# v3a.net
KiCad netlist of a schematic drawn in EAGLE
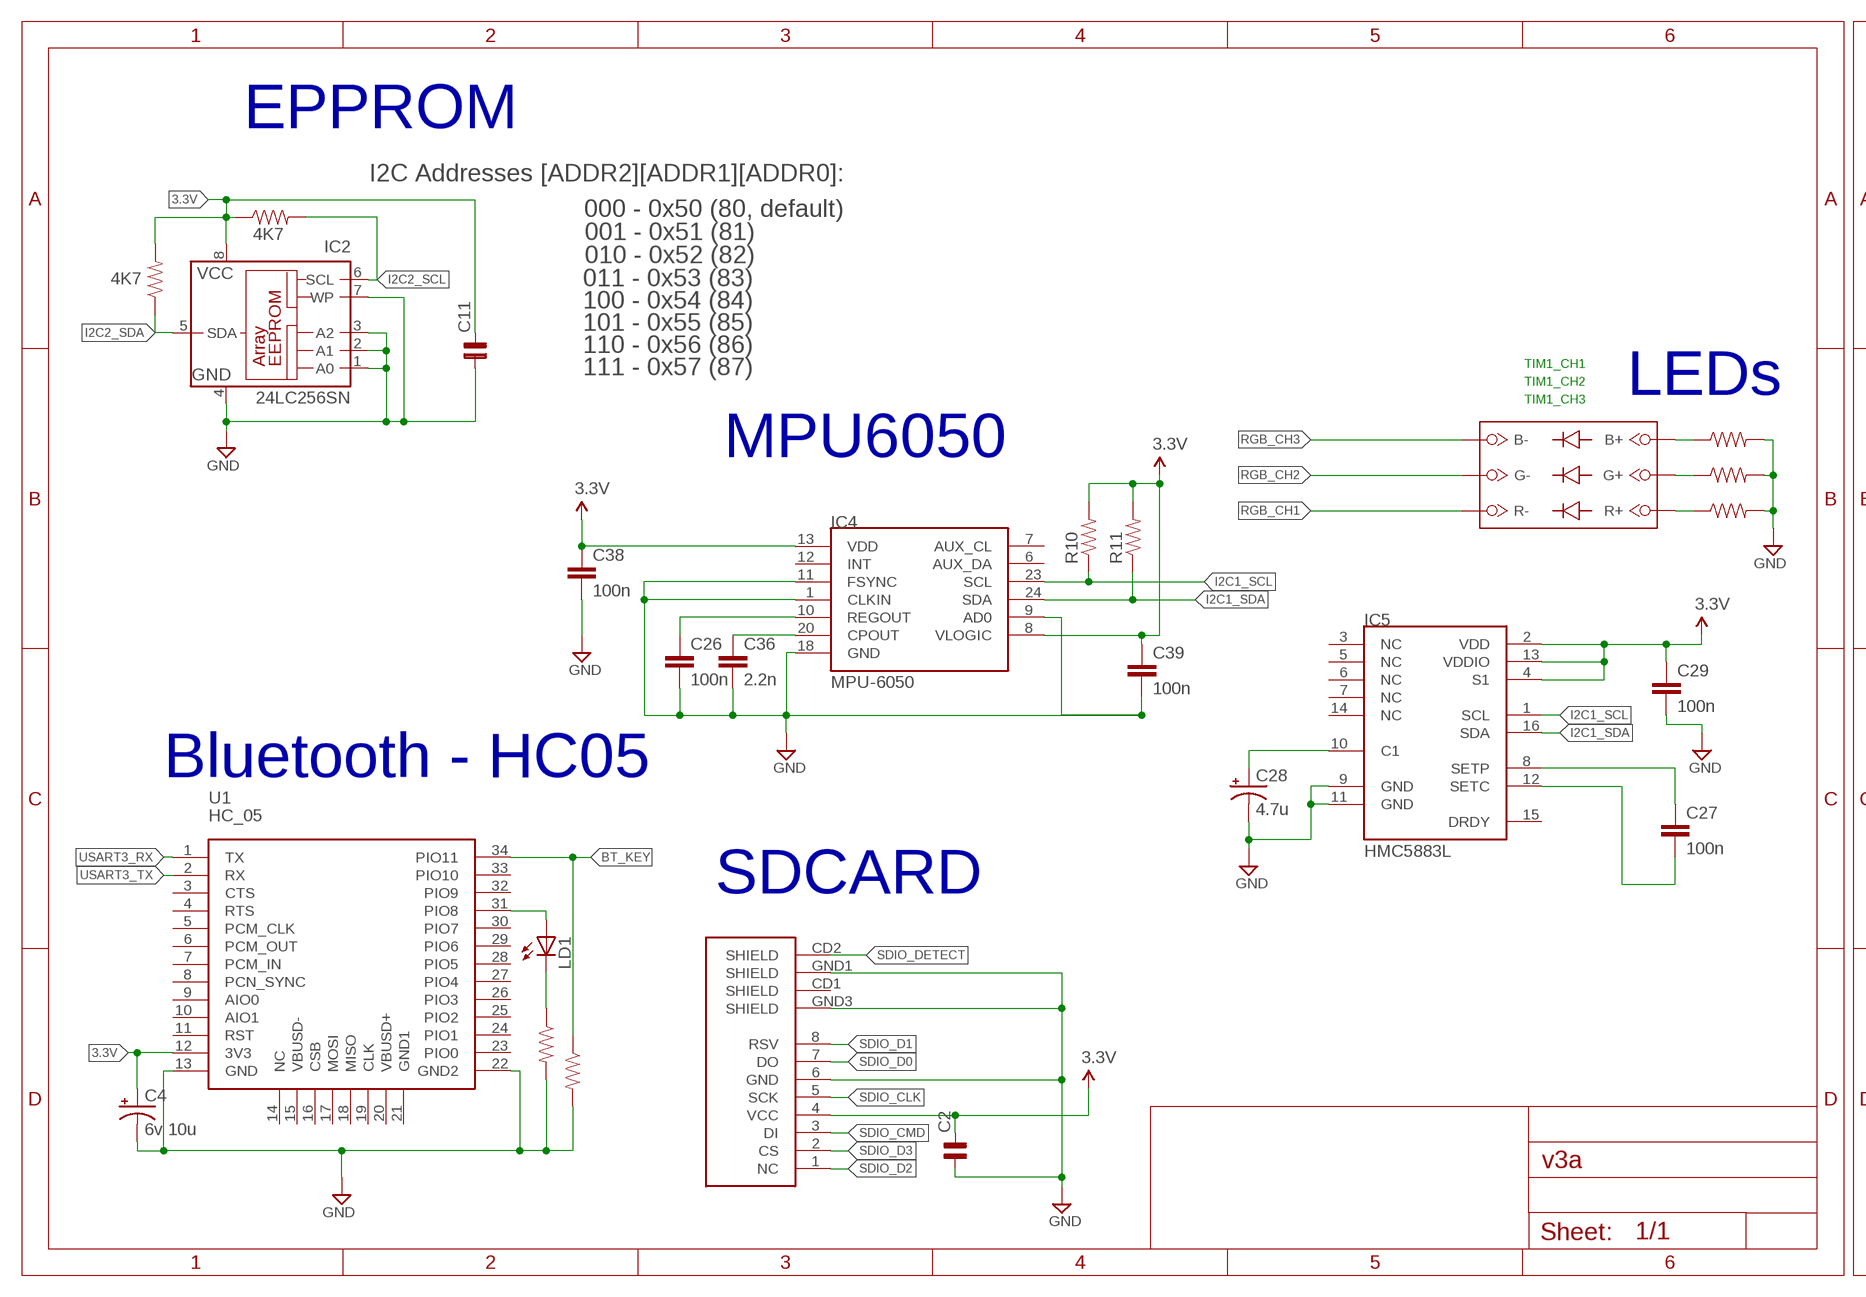
[diagram p0: schematic, sheet 1, part 1 of 2]
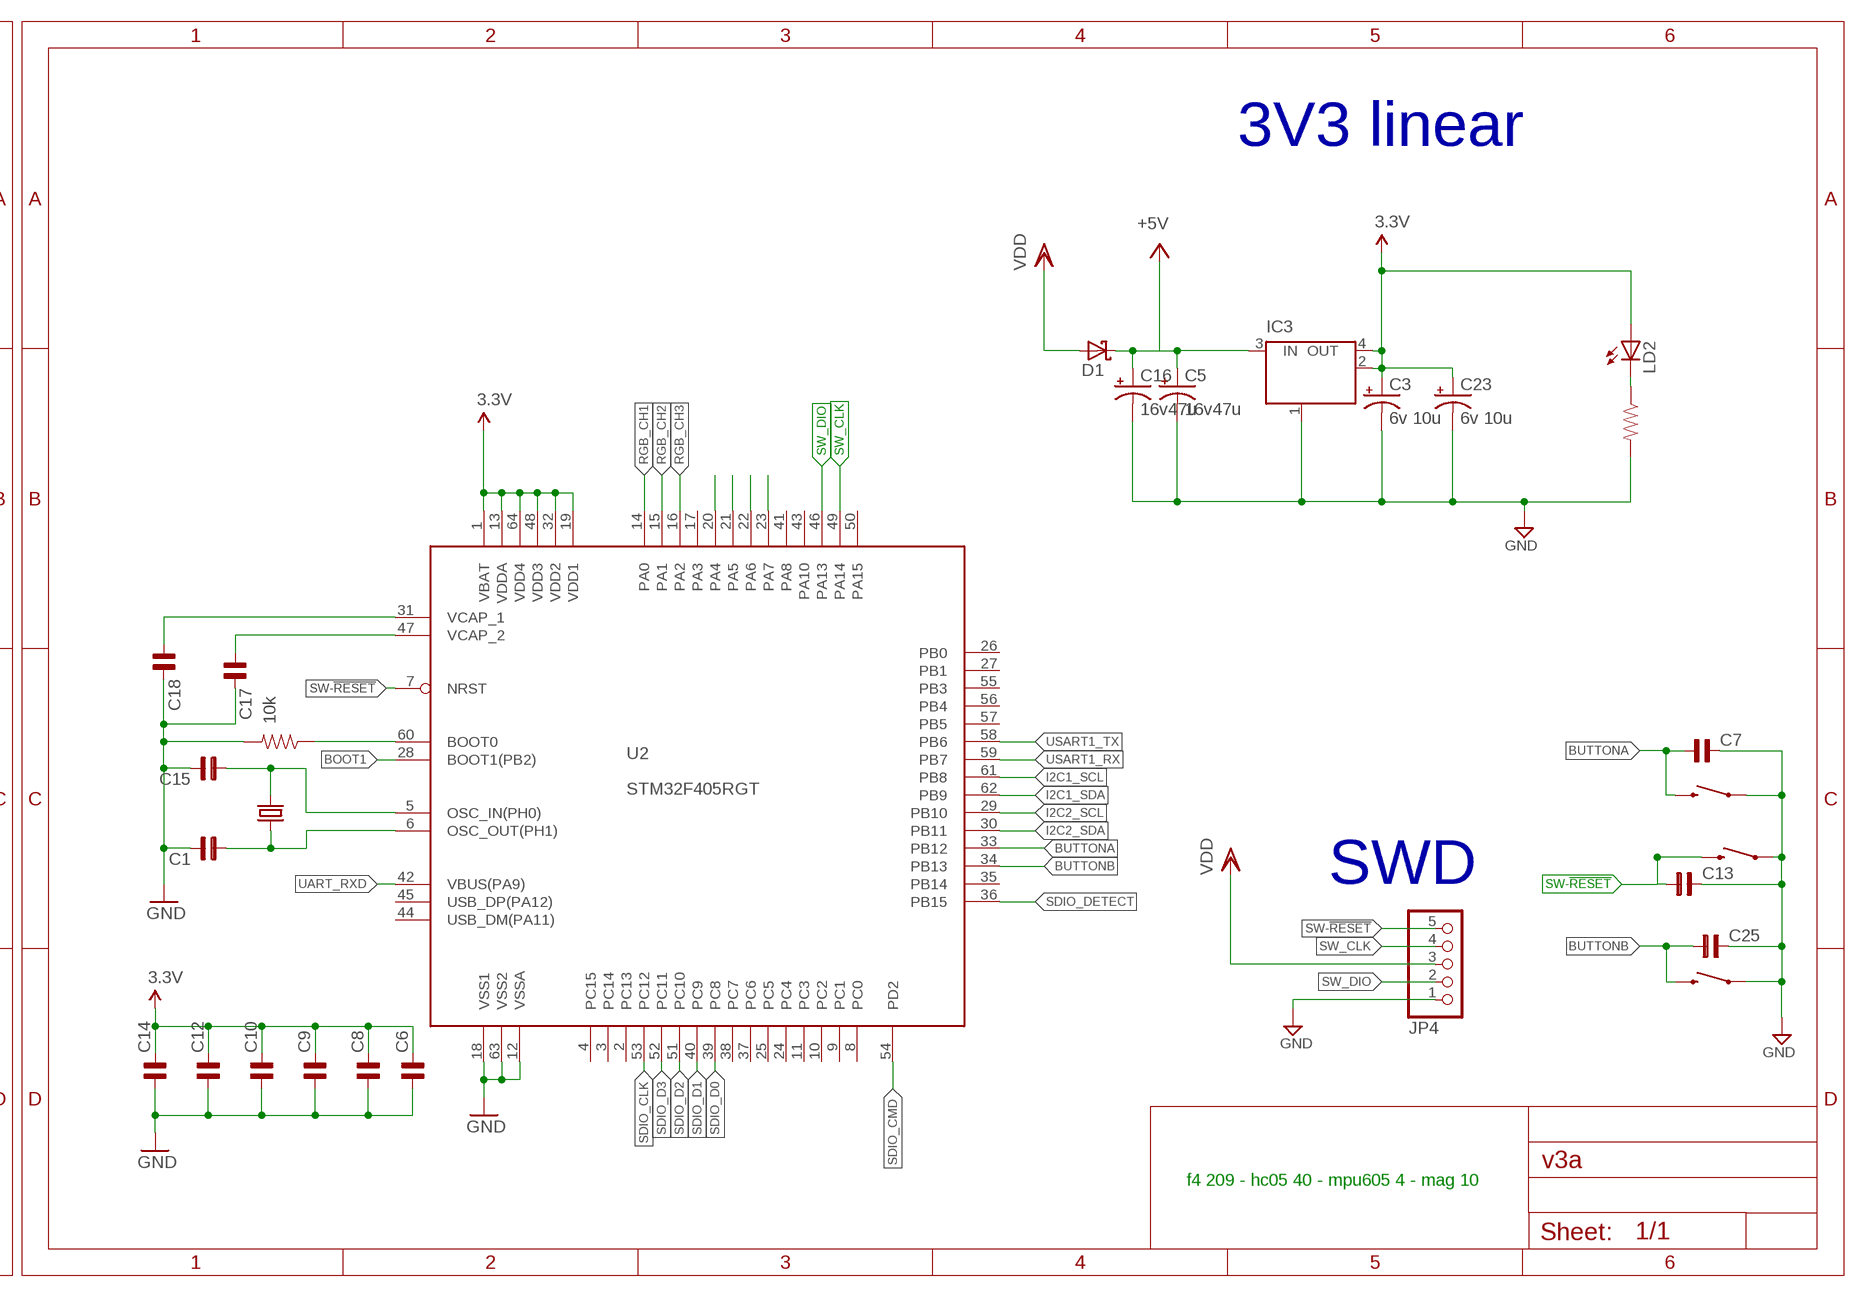
[diagram p1: schematic, sheet 1, part 2 of 2]

(export (version "E")
  (design (tool "Eeschema 10.0.6"))
  (components
    (comp (ref "C1")
      (value "C-NP-SMD-0603")
      (footprint "eagle-import:C-0603")
      (libsource (lib "eagle-import") (part "C-NP-SMD-0603"))
    )
    (comp (ref "C2")
      (value "C-NP-SMD-0603")
      (footprint "eagle-import:C-0603")
      (libsource (lib "eagle-import") (part "C-NP-SMD-0603"))
    )
    (comp (ref "C3")
      (value "6v 10u")
      (footprint "eagle-import:SMC_C")
      (libsource (lib "eagle-import") (part "CPOL-USSMCC"))
    )
    (comp (ref "C4")
      (value "6v 10u")
      (footprint "eagle-import:SMC_A")
      (libsource (lib "eagle-import") (part "CPOL-USSMCA"))
    )
    (comp (ref "C5")
      (value "16v47u")
      (footprint "eagle-import:SMC_C")
      (libsource (lib "eagle-import") (part "CPOL-USSMCC"))
    )
    (comp (ref "C6")
      (value "C-NP-SMD-0603")
      (footprint "eagle-import:C-0603")
      (libsource (lib "eagle-import") (part "C-NP-SMD-0603"))
    )
    (comp (ref "C7")
      (value "C-NP-SMD-0603")
      (footprint "eagle-import:C-0603")
      (libsource (lib "eagle-import") (part "C-NP-SMD-0603"))
    )
    (comp (ref "C8")
      (value "C-NP-SMD-0603")
      (footprint "eagle-import:C-0603")
      (libsource (lib "eagle-import") (part "C-NP-SMD-0603"))
    )
    (comp (ref "C9")
      (value "C-NP-SMD-0603")
      (footprint "eagle-import:C-0603")
      (libsource (lib "eagle-import") (part "C-NP-SMD-0603"))
    )
    (comp (ref "C10")
      (value "C-NP-SMD-0603")
      (footprint "eagle-import:C-0603")
      (libsource (lib "eagle-import") (part "C-NP-SMD-0603"))
    )
    (comp (ref "C11")
      (value "C-NP-SMD-0603")
      (footprint "eagle-import:C-0603")
      (libsource (lib "eagle-import") (part "C-NP-SMD-0603"))
    )
    (comp (ref "C12")
      (value "C-NP-SMD-0603")
      (footprint "eagle-import:C-0603")
      (libsource (lib "eagle-import") (part "C-NP-SMD-0603"))
    )
    (comp (ref "C13")
      (value "C-NP-SMD-0603")
      (footprint "eagle-import:C-0603")
      (libsource (lib "eagle-import") (part "C-NP-SMD-0603"))
    )
    (comp (ref "C14")
      (value "C-NP-SMD-0603")
      (footprint "eagle-import:C-0603")
      (libsource (lib "eagle-import") (part "C-NP-SMD-0603"))
    )
    (comp (ref "C15")
      (value "C-NP-SMD-0603")
      (footprint "eagle-import:C-0603")
      (libsource (lib "eagle-import") (part "C-NP-SMD-0603"))
    )
    (comp (ref "C16")
      (value "16v47u")
      (footprint "eagle-import:SMC_C")
      (libsource (lib "eagle-import") (part "CPOL-USSMCC"))
    )
    (comp (ref "C17")
      (value "C-NP-SMD-0603")
      (footprint "eagle-import:C-0603")
      (libsource (lib "eagle-import") (part "C-NP-SMD-0603"))
    )
    (comp (ref "C18")
      (value "C-NP-SMD-0603")
      (footprint "eagle-import:C-0603")
      (libsource (lib "eagle-import") (part "C-NP-SMD-0603"))
    )
    (comp (ref "C23")
      (value "6v 10u")
      (footprint "eagle-import:SMC_C")
      (libsource (lib "eagle-import") (part "CPOL-USSMCC"))
    )
    (comp (ref "C25")
      (value "C-NP-SMD-0603")
      (footprint "eagle-import:C-0603")
      (libsource (lib "eagle-import") (part "C-NP-SMD-0603"))
    )
    (comp (ref "C26")
      (value "100n")
      (footprint "eagle-import:SPARKFUN_0603-CAP")
      (libsource (lib "eagle-import") (part "SPARKFUN_CAP0603-CAP"))
    )
    (comp (ref "C27")
      (value "100n")
      (footprint "eagle-import:SPARKFUN_0603-CAP")
      (libsource (lib "eagle-import") (part "SPARKFUN_CAP0603-CAP"))
    )
    (comp (ref "C28")
      (value "4.7u")
      (footprint "eagle-import:SMC_A")
      (libsource (lib "eagle-import") (part "CPOL-USSMCA"))
    )
    (comp (ref "C29")
      (value "100n")
      (footprint "eagle-import:SPARKFUN_0603-CAP")
      (libsource (lib "eagle-import") (part "SPARKFUN_CAP0603-CAP"))
    )
    (comp (ref "C36")
      (value "2.2n")
      (footprint "eagle-import:SPARKFUN_0603-CAP")
      (libsource (lib "eagle-import") (part "SPARKFUN_CAP0603-CAP"))
    )
    (comp (ref "C38")
      (value "100n")
      (footprint "eagle-import:SPARKFUN_0603-CAP")
      (libsource (lib "eagle-import") (part "SPARKFUN_CAP0603-CAP"))
    )
    (comp (ref "C39")
      (value "100n")
      (footprint "eagle-import:SPARKFUN_0603-CAP")
      (libsource (lib "eagle-import") (part "SPARKFUN_CAP0603-CAP"))
    )
    (comp (ref "D1")
      (value "MBRS330T3")
      (footprint "eagle-import:SMC")
      (libsource (lib "eagle-import") (part "MBRS30T33"))
    )
    (comp (ref "IC2")
      (value "24LC256SN")
      (footprint "eagle-import:SO-08")
      (fields (field (name "MF") "MICROCHIP") (field (name "MPN") "24LC256-I/SN"))
      (libsource (lib "eagle-import") (part "24SNLC256"))
    )
    (comp (ref "IC3")
      (value "LINEAR_MC33269ST-3.3T3")
      (footprint "eagle-import:LINEAR_SOT223")
      (libsource (lib "eagle-import") (part "LINEAR_MC33269ST-3.3T3"))
    )
    (comp (ref "IC4")
      (value "MPU-6050")
      (footprint "eagle-import:TESTING_QFN-24-4MM2")
      (libsource (lib "eagle-import") (part "TESTING_MPU-6050-1"))
    )
    (comp (ref "IC5")
      (value "HMC5883L")
      (footprint "eagle-import:SPARKFUN_16LPCC")
      (libsource (lib "eagle-import") (part "SPARKFUN_HMC5883LSMD"))
    )
    (comp (ref "JP4")
      (value "PINHD-1X5_2.54-90°")
      (footprint "eagle-import:1X05_90")
      (libsource (lib "eagle-import") (part "PINHD-1X5_2.54-90°"))
    )
    (comp (ref "LD1")
      (value "LEDCHIPLED_0603")
      (footprint "eagle-import:CHIPLED_0603")
      (libsource (lib "eagle-import") (part "LEDCHIPLED_0603"))
    )
    (comp (ref "LD2")
      (value "LEDCHIPLED_0603")
      (footprint "eagle-import:CHIPLED_0603")
      (libsource (lib "eagle-import") (part "LEDCHIPLED_0603"))
    )
    (comp (ref "R1")
      (value "10K")
      (footprint "eagle-import:SPARKFUN_0603-RES")
      (libsource (lib "eagle-import") (part "Robotech_RCL_SPARKFUN_RESISTOR0603-RES"))
    )
    (comp (ref "R2")
      (value "10K")
      (footprint "eagle-import:SPARKFUN_0603-RES")
      (libsource (lib "eagle-import") (part "Robotech_RCL_SPARKFUN_RESISTOR0603-RES"))
    )
    (comp (ref "R3")
      (value "10K")
      (footprint "eagle-import:SPARKFUN_0603-RES")
      (libsource (lib "eagle-import") (part "Robotech_RCL_SPARKFUN_RESISTOR0603-RES"))
    )
    (comp (ref "R5")
      (value "10K")
      (footprint "eagle-import:SPARKFUN_0603-RES")
      (libsource (lib "eagle-import") (part "Robotech_RCL_SPARKFUN_RESISTOR0603-RES"))
    )
    (comp (ref "R6")
      (value "10K")
      (footprint "eagle-import:SPARKFUN_0603-RES")
      (libsource (lib "eagle-import") (part "Robotech_RCL_SPARKFUN_RESISTOR0603-RES"))
    )
    (comp (ref "R7")
      (value "10k")
      (footprint "eagle-import:SPARKFUN_0603-RES")
      (libsource (lib "eagle-import") (part "Robotech_RCL_SPARKFUN_RESISTOR0603-RES"))
    )
    (comp (ref "R9")
      (value "10K")
      (footprint "eagle-import:SPARKFUN_0603-RES")
      (libsource (lib "eagle-import") (part "Robotech_RCL_SPARKFUN_RESISTOR0603-RES"))
    )
    (comp (ref "R10")
      (value "SPARKFUN_RESISTOR0603-RES")
      (footprint "eagle-import:SPARKFUN_0603-RES")
      (libsource (lib "eagle-import") (part "SPARKFUN_RESISTOR0603-RES"))
    )
    (comp (ref "R11")
      (value "SPARKFUN_RESISTOR0603-RES")
      (footprint "eagle-import:SPARKFUN_0603-RES")
      (libsource (lib "eagle-import") (part "SPARKFUN_RESISTOR0603-RES"))
    )
    (comp (ref "R15")
      (value "4K7")
      (footprint "eagle-import:SPARKFUN_0603-RES")
      (libsource (lib "eagle-import") (part "Robotech_RCL_SPARKFUN_RESISTOR0603-RES"))
    )
    (comp (ref "R16")
      (value "4K7")
      (footprint "eagle-import:SPARKFUN_0603-RES")
      (libsource (lib "eagle-import") (part "Robotech_RCL_SPARKFUN_RESISTOR0603-RES"))
    )
    (comp (ref "S1")
      (value "RESET")
      (footprint "eagle-import:TACTILE-SWITCH-1101NE")
      (fields (field (name "PARTNO") "EVQ-P7J01P"))
      (libsource (lib "eagle-import") (part "SWITCH-MOMENTARY-2-SMD-1101NE"))
    )
    (comp (ref "S2")
      (value "RESET")
      (footprint "eagle-import:TACTILE-SWITCH-1101NE")
      (fields (field (name "PARTNO") "EVQ-P7J01P"))
      (libsource (lib "eagle-import") (part "SWITCH-MOMENTARY-2-SMD-1101NE"))
    )
    (comp (ref "S4")
      (value "RESET")
      (footprint "eagle-import:TACTILE-SWITCH-1101NE")
      (fields (field (name "PARTNO") "EVQ-P7J01P"))
      (libsource (lib "eagle-import") (part "SWITCH-MOMENTARY-2-SMD-1101NE"))
    )
    (comp (ref "SDCARD2")
      (value "microSD Socket")
      (footprint "eagle-import:MICRO-SD-SOCKET-PP")
      (libsource (lib "eagle-import") (part "USD-SOCKETNEW"))
    )
    (comp (ref "U$12")
      (value "RGB_LED")
      (footprint "eagle-import:SMD")
      (libsource (lib "eagle-import") (part "RGB_LED"))
    )
    (comp (ref "U1")
      (value "HC_05")
      (footprint "eagle-import:BLUETOOTH_SMD")
      (libsource (lib "eagle-import") (part "HC_05"))
    )
    (comp (ref "U2")
      (value "STM32F405RGT")
      (footprint "eagle-import:LQFP64")
      (libsource (lib "eagle-import") (part "STM32F405RGT"))
    )
    (comp (ref "Y2")
      (value "CRYSTALHC49US")
      (footprint "eagle-import:HC49US")
      (libsource (lib "eagle-import") (part "CRYSTALHC49US"))
    )
  )
  (nets
    (net (code "1") (name "+5V") (class "Default")
      (node (ref "C16") (pin "+") (pinfunction "+_+") (pintype "passive"))
      (node (ref "C5") (pin "+") (pinfunction "+_+") (pintype "passive"))
      (node (ref "D1") (pin "C") (pinfunction "C_C") (pintype "passive"))
      (node (ref "IC3") (pin "3") (pinfunction "IN_3") (pintype "input"))
    )
    (net (code "2") (name "/SW-~{RESET}") (class "Default")
      (node (ref "C13") (pin "1") (pinfunction "1_1") (pintype "passive"))
      (node (ref "JP4") (pin "5") (pinfunction "5_5") (pintype "passive"))
      (node (ref "S1") (pin "P$2") (pinfunction "2_P$2") (pintype "passive"))
      (node (ref "U2") (pin "7") (pinfunction "NRST_7") (pintype "input"))
    )
    (net (code "3") (name "3.3V") (class "Default")
      (node (ref "C10") (pin "2") (pinfunction "2_2") (pintype "passive"))
      (node (ref "C11") (pin "2") (pinfunction "2_2") (pintype "passive"))
      (node (ref "C12") (pin "2") (pinfunction "2_2") (pintype "passive"))
      (node (ref "C14") (pin "2") (pinfunction "2_2") (pintype "passive"))
      (node (ref "C2") (pin "2") (pinfunction "2_2") (pintype "passive"))
      (node (ref "C23") (pin "+") (pinfunction "+_+") (pintype "passive"))
      (node (ref "C29") (pin "1") (pinfunction "1_1") (pintype "passive"))
      (node (ref "C3") (pin "+") (pinfunction "+_+") (pintype "passive"))
      (node (ref "C38") (pin "1") (pinfunction "1_1") (pintype "passive"))
      (node (ref "C39") (pin "1") (pinfunction "1_1") (pintype "passive"))
      (node (ref "C4") (pin "+") (pinfunction "+_+") (pintype "passive"))
      (node (ref "C6") (pin "2") (pinfunction "2_2") (pintype "passive"))
      (node (ref "C8") (pin "2") (pinfunction "2_2") (pintype "passive"))
      (node (ref "C9") (pin "2") (pinfunction "2_2") (pintype "passive"))
      (node (ref "IC2") (pin "8") (pinfunction "VCC_8") (pintype "power_in"))
      (node (ref "IC3") (pin "2") (pinfunction "OUT_2") (pintype "passive"))
      (node (ref "IC3") (pin "4") (pinfunction "OUT_4") (pintype "passive"))
      (node (ref "IC4") (pin "13") (pinfunction "VDD_13") (pintype "bidirectional"))
      (node (ref "IC4") (pin "8") (pinfunction "VLOGIC_8") (pintype "bidirectional"))
      (node (ref "IC5") (pin "13") (pinfunction "VDDIO_13") (pintype "bidirectional"))
      (node (ref "IC5") (pin "2") (pinfunction "VDD_2") (pintype "bidirectional"))
      (node (ref "IC5") (pin "4") (pinfunction "S1_4") (pintype "bidirectional"))
      (node (ref "LD2") (pin "A") (pinfunction "A_A") (pintype "passive"))
      (node (ref "R10") (pin "2") (pinfunction "2_2") (pintype "passive"))
      (node (ref "R11") (pin "2") (pinfunction "2_2") (pintype "passive"))
      (node (ref "R15") (pin "1") (pinfunction "1_1") (pintype "passive"))
      (node (ref "R16") (pin "2") (pinfunction "2_2") (pintype "passive"))
      (node (ref "SDCARD2") (pin "4") (pinfunction "VCC_4") (pintype "bidirectional"))
      (node (ref "U1") (pin "12") (pinfunction "3V3_12") (pintype "bidirectional"))
      (node (ref "U2") (pin "1") (pinfunction "VBAT_1") (pintype "power_in"))
      (node (ref "U2") (pin "13") (pinfunction "VDDA_13") (pintype "power_in"))
      (node (ref "U2") (pin "19") (pinfunction "VDD1_19") (pintype "power_in"))
      (node (ref "U2") (pin "32") (pinfunction "VDD2_32") (pintype "power_in"))
      (node (ref "U2") (pin "48") (pinfunction "VDD3_48") (pintype "power_in"))
      (node (ref "U2") (pin "64") (pinfunction "VDD4_64") (pintype "power_in"))
    )
    (net (code "4") (name "BOOT1") (class "Default")
      (node (ref "U2") (pin "28") (pinfunction "BOOT1(PB2)_28") (pintype "input"))
    )
    (net (code "5") (name "BT_KEY") (class "Default")
      (node (ref "R5") (pin "1") (pinfunction "1_1") (pintype "passive"))
      (node (ref "U1") (pin "34") (pinfunction "PIO11_34") (pintype "bidirectional"))
    )
    (net (code "6") (name "BUTTONA") (class "Default")
      (node (ref "C7") (pin "1") (pinfunction "1_1") (pintype "passive"))
      (node (ref "S4") (pin "P$2") (pinfunction "2_P$2") (pintype "passive"))
      (node (ref "U2") (pin "33") (pinfunction "PB12_33") (pintype "bidirectional"))
    )
    (net (code "7") (name "BUTTONB") (class "Default")
      (node (ref "C25") (pin "1") (pinfunction "1_1") (pintype "passive"))
      (node (ref "S2") (pin "P$2") (pinfunction "2_P$2") (pintype "passive"))
      (node (ref "U2") (pin "34") (pinfunction "PB13_34") (pintype "bidirectional"))
    )
    (net (code "8") (name "GND") (class "Default")
      (node (ref "C1") (pin "2") (pinfunction "2_2") (pintype "passive"))
      (node (ref "C10") (pin "1") (pinfunction "1_1") (pintype "passive"))
      (node (ref "C11") (pin "1") (pinfunction "1_1") (pintype "passive"))
      (node (ref "C12") (pin "1") (pinfunction "1_1") (pintype "passive"))
      (node (ref "C13") (pin "2") (pinfunction "2_2") (pintype "passive"))
      (node (ref "C14") (pin "1") (pinfunction "1_1") (pintype "passive"))
      (node (ref "C15") (pin "2") (pinfunction "2_2") (pintype "passive"))
      (node (ref "C16") (pin "-") (pinfunction "-_-") (pintype "passive"))
      (node (ref "C17") (pin "2") (pinfunction "2_2") (pintype "passive"))
      (node (ref "C18") (pin "2") (pinfunction "2_2") (pintype "passive"))
      (node (ref "C2") (pin "1") (pinfunction "1_1") (pintype "passive"))
      (node (ref "C23") (pin "-") (pinfunction "-_-") (pintype "passive"))
      (node (ref "C25") (pin "2") (pinfunction "2_2") (pintype "passive"))
      (node (ref "C26") (pin "2") (pinfunction "2_2") (pintype "passive"))
      (node (ref "C28") (pin "-") (pinfunction "-_-") (pintype "passive"))
      (node (ref "C29") (pin "2") (pinfunction "2_2") (pintype "passive"))
      (node (ref "C3") (pin "-") (pinfunction "-_-") (pintype "passive"))
      (node (ref "C36") (pin "2") (pinfunction "2_2") (pintype "passive"))
      (node (ref "C38") (pin "2") (pinfunction "2_2") (pintype "passive"))
      (node (ref "C39") (pin "2") (pinfunction "2_2") (pintype "passive"))
      (node (ref "C4") (pin "-") (pinfunction "-_-") (pintype "passive"))
      (node (ref "C5") (pin "-") (pinfunction "-_-") (pintype "passive"))
      (node (ref "C6") (pin "1") (pinfunction "1_1") (pintype "passive"))
      (node (ref "C7") (pin "2") (pinfunction "2_2") (pintype "passive"))
      (node (ref "C8") (pin "1") (pinfunction "1_1") (pintype "passive"))
      (node (ref "C9") (pin "1") (pinfunction "1_1") (pintype "passive"))
      (node (ref "IC2") (pin "1") (pinfunction "A0_1") (pintype "input"))
      (node (ref "IC2") (pin "2") (pinfunction "A1_2") (pintype "input"))
      (node (ref "IC2") (pin "3") (pinfunction "A2_3") (pintype "input"))
      (node (ref "IC2") (pin "4") (pinfunction "GND_4") (pintype "power_in"))
      (node (ref "IC2") (pin "7") (pinfunction "WP_7") (pintype "input"))
      (node (ref "IC3") (pin "1") (pinfunction "GND/ADJ_1") (pintype "input"))
      (node (ref "IC4") (pin "1") (pinfunction "CLKIN_1") (pintype "bidirectional"))
      (node (ref "IC4") (pin "11") (pinfunction "FSYNC_11") (pintype "bidirectional"))
      (node (ref "IC4") (pin "18") (pinfunction "GND_18") (pintype "bidirectional"))
      (node (ref "IC4") (pin "9") (pinfunction "AD0_9") (pintype "bidirectional"))
      (node (ref "IC5") (pin "11") (pinfunction "GND_11") (pintype "bidirectional"))
      (node (ref "IC5") (pin "9") (pinfunction "GND_9") (pintype "bidirectional"))
      (node (ref "JP4") (pin "1") (pinfunction "1_1") (pintype "passive"))
      (node (ref "R1") (pin "2") (pinfunction "2_2") (pintype "passive"))
      (node (ref "R2") (pin "2") (pinfunction "2_2") (pintype "passive"))
      (node (ref "R3") (pin "2") (pinfunction "2_2") (pintype "passive"))
      (node (ref "R5") (pin "2") (pinfunction "2_2") (pintype "passive"))
      (node (ref "R6") (pin "2") (pinfunction "2_2") (pintype "passive"))
      (node (ref "R7") (pin "2") (pinfunction "2_2") (pintype "passive"))
      (node (ref "R9") (pin "2") (pinfunction "2_2") (pintype "passive"))
      (node (ref "S1") (pin "P$1") (pinfunction "1_P$1") (pintype "passive"))
      (node (ref "S2") (pin "P$1") (pinfunction "1_P$1") (pintype "passive"))
      (node (ref "S4") (pin "P$1") (pinfunction "1_P$1") (pintype "passive"))
      (node (ref "SDCARD2") (pin "6") (pinfunction "GND_6") (pintype "bidirectional"))
      (node (ref "SDCARD2") (pin "GND1") (pinfunction "SHIELD_GND1") (pintype "bidirectional"))
      (node (ref "SDCARD2") (pin "GND3") (pinfunction "SHIELD_GND3") (pintype "bidirectional"))
      (node (ref "U1") (pin "13") (pinfunction "GND_13") (pintype "bidirectional"))
      (node (ref "U1") (pin "22") (pinfunction "GND2_22") (pintype "bidirectional"))
      (node (ref "U2") (pin "12") (pinfunction "VSSA_12") (pintype "power_in"))
      (node (ref "U2") (pin "18") (pinfunction "VSS1_18") (pintype "power_in"))
      (node (ref "U2") (pin "63") (pinfunction "VSS2_63") (pintype "power_in"))
    )
    (net (code "9") (name "I2C1_SCL") (class "Default")
      (node (ref "IC4") (pin "23") (pinfunction "SCL_23") (pintype "bidirectional"))
      (node (ref "IC5") (pin "1") (pinfunction "SCL_1") (pintype "bidirectional"))
      (node (ref "R10") (pin "1") (pinfunction "1_1") (pintype "passive"))
      (node (ref "U2") (pin "61") (pinfunction "PB8_61") (pintype "bidirectional"))
    )
    (net (code "10") (name "I2C1_SDA") (class "Default")
      (node (ref "IC4") (pin "24") (pinfunction "SDA_24") (pintype "bidirectional"))
      (node (ref "IC5") (pin "16") (pinfunction "SDA_16") (pintype "bidirectional"))
      (node (ref "R11") (pin "1") (pinfunction "1_1") (pintype "passive"))
      (node (ref "U2") (pin "62") (pinfunction "PB9_62") (pintype "bidirectional"))
    )
    (net (code "11") (name "I2C2_SCL") (class "Default")
      (node (ref "IC2") (pin "6") (pinfunction "SCL_6") (pintype "input"))
      (node (ref "R15") (pin "2") (pinfunction "2_2") (pintype "passive"))
      (node (ref "U2") (pin "29") (pinfunction "PB10_29") (pintype "bidirectional"))
    )
    (net (code "12") (name "I2C2_SDA") (class "Default")
      (node (ref "IC2") (pin "5") (pinfunction "SDA_5") (pintype "bidirectional"))
      (node (ref "R16") (pin "1") (pinfunction "1_1") (pintype "passive"))
      (node (ref "U2") (pin "30") (pinfunction "PB11_30") (pintype "bidirectional"))
    )
    (net (code "13") (name "Net-(IC4-CPOUT)") (class "Default")
      (node (ref "C36") (pin "1") (pinfunction "1_1") (pintype "passive"))
      (node (ref "IC4") (pin "20") (pinfunction "CPOUT_20") (pintype "bidirectional"))
    )
    (net (code "14") (name "Net-(IC4-REGOUT)") (class "Default")
      (node (ref "C26") (pin "1") (pinfunction "1_1") (pintype "passive"))
      (node (ref "IC4") (pin "10") (pinfunction "REGOUT_10") (pintype "bidirectional"))
    )
    (net (code "15") (name "Net-(IC5-C1)") (class "Default")
      (node (ref "C28") (pin "+") (pinfunction "+_+") (pintype "passive"))
      (node (ref "IC5") (pin "10") (pinfunction "C1_10") (pintype "bidirectional"))
    )
    (net (code "16") (name "Net-(IC5-SETC)") (class "Default")
      (node (ref "C27") (pin "2") (pinfunction "2_2") (pintype "passive"))
      (node (ref "IC5") (pin "12") (pinfunction "SETC_12") (pintype "bidirectional"))
    )
    (net (code "17") (name "Net-(IC5-SETP)") (class "Default")
      (node (ref "C27") (pin "1") (pinfunction "1_1") (pintype "passive"))
      (node (ref "IC5") (pin "8") (pinfunction "SETP_8") (pintype "bidirectional"))
    )
    (net (code "18") (name "Net-(LD1-PadC)") (class "Default")
      (node (ref "LD1") (pin "C") (pinfunction "C_C") (pintype "passive"))
      (node (ref "R9") (pin "1") (pinfunction "1_1") (pintype "passive"))
    )
    (net (code "19") (name "Net-(LD2-PadC)") (class "Default")
      (node (ref "LD2") (pin "C") (pinfunction "C_C") (pintype "passive"))
      (node (ref "R1") (pin "1") (pinfunction "1_1") (pintype "passive"))
    )
    (net (code "20") (name "Net-(R2-Pad1)") (class "Default")
      (node (ref "R2") (pin "1") (pinfunction "1_1") (pintype "passive"))
      (node (ref "U$12") (pin "B+") (pinfunction "B+_B+") (pintype "bidirectional"))
    )
    (net (code "21") (name "Net-(R3-Pad1)") (class "Default")
      (node (ref "R3") (pin "1") (pinfunction "1_1") (pintype "passive"))
      (node (ref "U$12") (pin "G+") (pinfunction "G+_G+") (pintype "bidirectional"))
    )
    (net (code "22") (name "Net-(R6-Pad1)") (class "Default")
      (node (ref "R6") (pin "1") (pinfunction "1_1") (pintype "passive"))
      (node (ref "U$12") (pin "R+") (pinfunction "R+_R+") (pintype "bidirectional"))
    )
    (net (code "23") (name "Net-(U1-PIO8)") (class "Default")
      (node (ref "LD1") (pin "A") (pinfunction "A_A") (pintype "passive"))
      (node (ref "U1") (pin "31") (pinfunction "PIO8_31") (pintype "bidirectional"))
    )
    (net (code "24") (name "Net-(U2-BOOT0)") (class "Default")
      (node (ref "R7") (pin "1") (pinfunction "1_1") (pintype "passive"))
      (node (ref "U2") (pin "60") (pinfunction "BOOT0_60") (pintype "input"))
    )
    (net (code "25") (name "Net-(U2-OSC_IN(PH0))") (class "Default")
      (node (ref "C15") (pin "1") (pinfunction "1_1") (pintype "passive"))
      (node (ref "U2") (pin "5") (pinfunction "OSC_IN(PH0)_5") (pintype "bidirectional"))
      (node (ref "Y2") (pin "2") (pinfunction "2_2") (pintype "passive"))
    )
    (net (code "26") (name "Net-(U2-OSC_OUT(PH1))") (class "Default")
      (node (ref "C1") (pin "1") (pinfunction "1_1") (pintype "passive"))
      (node (ref "U2") (pin "6") (pinfunction "OSC_OUT(PH1)_6") (pintype "bidirectional"))
      (node (ref "Y2") (pin "1") (pinfunction "1_1") (pintype "passive"))
    )
    (net (code "27") (name "Net-(U2-VCAP_1)") (class "Default")
      (node (ref "C18") (pin "1") (pinfunction "1_1") (pintype "passive"))
      (node (ref "U2") (pin "31") (pinfunction "VCAP_1_31") (pintype "bidirectional"))
    )
    (net (code "28") (name "Net-(U2-VCAP_2)") (class "Default")
      (node (ref "C17") (pin "1") (pinfunction "1_1") (pintype "passive"))
      (node (ref "U2") (pin "47") (pinfunction "VCAP_2_47") (pintype "bidirectional"))
    )
    (net (code "29") (name "RGB_CH1") (class "Default")
      (node (ref "U$12") (pin "R-") (pinfunction "R-_R-") (pintype "bidirectional"))
      (node (ref "U2") (pin "14") (pinfunction "PA0_14") (pintype "bidirectional"))
    )
    (net (code "30") (name "RGB_CH2") (class "Default")
      (node (ref "U$12") (pin "G-") (pinfunction "G-_G-") (pintype "bidirectional"))
      (node (ref "U2") (pin "15") (pinfunction "PA1_15") (pintype "bidirectional"))
    )
    (net (code "31") (name "RGB_CH3") (class "Default")
      (node (ref "U$12") (pin "B-") (pinfunction "B-_B-") (pintype "bidirectional"))
      (node (ref "U2") (pin "16") (pinfunction "PA2_16") (pintype "bidirectional"))
    )
    (net (code "32") (name "SDIO_CLK") (class "Default")
      (node (ref "SDCARD2") (pin "5") (pinfunction "SCK_5") (pintype "bidirectional"))
      (node (ref "U2") (pin "53") (pinfunction "PC12_53") (pintype "bidirectional"))
    )
    (net (code "33") (name "SDIO_CMD") (class "Default")
      (node (ref "SDCARD2") (pin "3") (pinfunction "DI_3") (pintype "bidirectional"))
      (node (ref "U2") (pin "54") (pinfunction "PD2_54") (pintype "bidirectional"))
    )
    (net (code "34") (name "SDIO_D0") (class "Default")
      (node (ref "SDCARD2") (pin "7") (pinfunction "DO_7") (pintype "bidirectional"))
      (node (ref "U2") (pin "39") (pinfunction "PC8_39") (pintype "bidirectional"))
    )
    (net (code "35") (name "SDIO_D1") (class "Default")
      (node (ref "SDCARD2") (pin "8") (pinfunction "RSV_8") (pintype "bidirectional"))
      (node (ref "U2") (pin "40") (pinfunction "PC9_40") (pintype "bidirectional"))
    )
    (net (code "36") (name "SDIO_D2") (class "Default")
      (node (ref "SDCARD2") (pin "1") (pinfunction "NC_1") (pintype "bidirectional"))
      (node (ref "U2") (pin "51") (pinfunction "PC10_51") (pintype "bidirectional"))
    )
    (net (code "37") (name "SDIO_D3") (class "Default")
      (node (ref "SDCARD2") (pin "2") (pinfunction "CS_2") (pintype "bidirectional"))
      (node (ref "U2") (pin "52") (pinfunction "PC11_52") (pintype "bidirectional"))
    )
    (net (code "38") (name "SDIO_DETECT") (class "Default")
      (node (ref "SDCARD2") (pin "CD2") (pinfunction "SHIELD_CD2") (pintype "bidirectional"))
      (node (ref "U2") (pin "36") (pinfunction "PB15_36") (pintype "bidirectional"))
    )
    (net (code "39") (name "SW_CLK") (class "Default")
      (node (ref "JP4") (pin "4") (pinfunction "4_4") (pintype "passive"))
      (node (ref "U2") (pin "49") (pinfunction "PA14_49") (pintype "bidirectional"))
    )
    (net (code "40") (name "SW_DIO") (class "Default")
      (node (ref "JP4") (pin "2") (pinfunction "2_2") (pintype "passive"))
      (node (ref "U2") (pin "46") (pinfunction "PA13_46") (pintype "bidirectional"))
    )
    (net (code "41") (name "UART_RXD") (class "Default")
      (node (ref "U2") (pin "42") (pinfunction "VBUS(PA9)_42") (pintype "bidirectional"))
    )
    (net (code "42") (name "USART1_RX") (class "Default")
      (node (ref "U2") (pin "59") (pinfunction "PB7_59") (pintype "bidirectional"))
    )
    (net (code "43") (name "USART1_TX") (class "Default")
      (node (ref "U2") (pin "58") (pinfunction "PB6_58") (pintype "bidirectional"))
    )
    (net (code "44") (name "USART3_RX") (class "Default")
      (node (ref "U1") (pin "1") (pinfunction "TX_1") (pintype "bidirectional"))
    )
    (net (code "45") (name "USART3_TX") (class "Default")
      (node (ref "U1") (pin "2") (pinfunction "RX_2") (pintype "bidirectional"))
    )
    (net (code "46") (name "VDD") (class "Default")
      (node (ref "D1") (pin "A") (pinfunction "A_A") (pintype "passive"))
      (node (ref "JP4") (pin "3") (pinfunction "3_3") (pintype "passive"))
    )
    (net (code "47") (name "unconnected-(IC4-AUX_CL-Pad7)") (class "Default")
      (node (ref "IC4") (pin "7") (pinfunction "AUX_CL_7") (pintype "bidirectional"))
    )
    (net (code "48") (name "unconnected-(IC4-AUX_DA-Pad6)") (class "Default")
      (node (ref "IC4") (pin "6") (pinfunction "AUX_DA_6") (pintype "bidirectional"))
    )
    (net (code "49") (name "unconnected-(IC4-INT-Pad12)") (class "Default")
      (node (ref "IC4") (pin "12") (pinfunction "INT_12") (pintype "bidirectional"))
    )
    (net (code "50") (name "unconnected-(IC5-DRDY-Pad15)") (class "Default")
      (node (ref "IC5") (pin "15") (pinfunction "DRDY_15") (pintype "bidirectional"))
    )
    (net (code "51") (name "unconnected-(IC5-NC-Pad3)") (class "Default")
      (node (ref "IC5") (pin "3") (pinfunction "NC_3") (pintype "bidirectional"))
    )
    (net (code "52") (name "unconnected-(IC5-NC-Pad5)") (class "Default")
      (node (ref "IC5") (pin "5") (pinfunction "NC_5") (pintype "bidirectional"))
    )
    (net (code "53") (name "unconnected-(IC5-NC-Pad6)") (class "Default")
      (node (ref "IC5") (pin "6") (pinfunction "NC_6") (pintype "bidirectional"))
    )
    (net (code "54") (name "unconnected-(IC5-NC-Pad7)") (class "Default")
      (node (ref "IC5") (pin "7") (pinfunction "NC_7") (pintype "bidirectional"))
    )
    (net (code "55") (name "unconnected-(IC5-NC-Pad14)") (class "Default")
      (node (ref "IC5") (pin "14") (pinfunction "NC_14") (pintype "bidirectional"))
    )
    (net (code "56") (name "unconnected-(SDCARD2-SHIELD-PadCD1)") (class "Default")
      (node (ref "SDCARD2") (pin "CD1") (pinfunction "SHIELD_CD1") (pintype "bidirectional"))
    )
    (net (code "57") (name "unconnected-(U1-AIO0-Pad9)") (class "Default")
      (node (ref "U1") (pin "9") (pinfunction "AIO0_9") (pintype "bidirectional"))
    )
    (net (code "58") (name "unconnected-(U1-AIO1-Pad10)") (class "Default")
      (node (ref "U1") (pin "10") (pinfunction "AIO1_10") (pintype "bidirectional"))
    )
    (net (code "59") (name "unconnected-(U1-CLK-Pad19)") (class "Default")
      (node (ref "U1") (pin "19") (pinfunction "CLK_19") (pintype "bidirectional"))
    )
    (net (code "60") (name "unconnected-(U1-CSB-Pad16)") (class "Default")
      (node (ref "U1") (pin "16") (pinfunction "CSB_16") (pintype "bidirectional"))
    )
    (net (code "61") (name "unconnected-(U1-CTS-Pad3)") (class "Default")
      (node (ref "U1") (pin "3") (pinfunction "CTS_3") (pintype "bidirectional"))
    )
    (net (code "62") (name "unconnected-(U1-GND1-Pad21)") (class "Default")
      (node (ref "U1") (pin "21") (pinfunction "GND1_21") (pintype "bidirectional"))
    )
    (net (code "63") (name "unconnected-(U1-MISO-Pad18)") (class "Default")
      (node (ref "U1") (pin "18") (pinfunction "MISO_18") (pintype "bidirectional"))
    )
    (net (code "64") (name "unconnected-(U1-MOSI-Pad17)") (class "Default")
      (node (ref "U1") (pin "17") (pinfunction "MOSI_17") (pintype "bidirectional"))
    )
    (net (code "65") (name "unconnected-(U1-NC-Pad14)") (class "Default")
      (node (ref "U1") (pin "14") (pinfunction "NC_14") (pintype "bidirectional"))
    )
    (net (code "66") (name "unconnected-(U1-PCM_CLK-Pad5)") (class "Default")
      (node (ref "U1") (pin "5") (pinfunction "PCM_CLK_5") (pintype "bidirectional"))
    )
    (net (code "67") (name "unconnected-(U1-PCM_IN-Pad7)") (class "Default")
      (node (ref "U1") (pin "7") (pinfunction "PCM_IN_7") (pintype "bidirectional"))
    )
    (net (code "68") (name "unconnected-(U1-PCM_OUT-Pad6)") (class "Default")
      (node (ref "U1") (pin "6") (pinfunction "PCM_OUT_6") (pintype "bidirectional"))
    )
    (net (code "69") (name "unconnected-(U1-PCN_SYNC-Pad8)") (class "Default")
      (node (ref "U1") (pin "8") (pinfunction "PCN_SYNC_8") (pintype "bidirectional"))
    )
    (net (code "70") (name "unconnected-(U1-PIO0-Pad23)") (class "Default")
      (node (ref "U1") (pin "23") (pinfunction "PIO0_23") (pintype "bidirectional"))
    )
    (net (code "71") (name "unconnected-(U1-PIO1-Pad24)") (class "Default")
      (node (ref "U1") (pin "24") (pinfunction "PIO1_24") (pintype "bidirectional"))
    )
    (net (code "72") (name "unconnected-(U1-PIO2-Pad25)") (class "Default")
      (node (ref "U1") (pin "25") (pinfunction "PIO2_25") (pintype "bidirectional"))
    )
    (net (code "73") (name "unconnected-(U1-PIO3-Pad26)") (class "Default")
      (node (ref "U1") (pin "26") (pinfunction "PIO3_26") (pintype "bidirectional"))
    )
    (net (code "74") (name "unconnected-(U1-PIO4-Pad27)") (class "Default")
      (node (ref "U1") (pin "27") (pinfunction "PIO4_27") (pintype "bidirectional"))
    )
    (net (code "75") (name "unconnected-(U1-PIO5-Pad28)") (class "Default")
      (node (ref "U1") (pin "28") (pinfunction "PIO5_28") (pintype "bidirectional"))
    )
    (net (code "76") (name "unconnected-(U1-PIO6-Pad29)") (class "Default")
      (node (ref "U1") (pin "29") (pinfunction "PIO6_29") (pintype "bidirectional"))
    )
    (net (code "77") (name "unconnected-(U1-PIO7-Pad30)") (class "Default")
      (node (ref "U1") (pin "30") (pinfunction "PIO7_30") (pintype "bidirectional"))
    )
    (net (code "78") (name "unconnected-(U1-PIO9-Pad32)") (class "Default")
      (node (ref "U1") (pin "32") (pinfunction "PIO9_32") (pintype "bidirectional"))
    )
    (net (code "79") (name "unconnected-(U1-PIO10-Pad33)") (class "Default")
      (node (ref "U1") (pin "33") (pinfunction "PIO10_33") (pintype "bidirectional"))
    )
    (net (code "80") (name "unconnected-(U1-RST-Pad11)") (class "Default")
      (node (ref "U1") (pin "11") (pinfunction "RST_11") (pintype "bidirectional"))
    )
    (net (code "81") (name "unconnected-(U1-RTS-Pad4)") (class "Default")
      (node (ref "U1") (pin "4") (pinfunction "RTS_4") (pintype "bidirectional"))
    )
    (net (code "82") (name "unconnected-(U1-VBUSD+-Pad20)") (class "Default")
      (node (ref "U1") (pin "20") (pinfunction "VBUSD+_20") (pintype "bidirectional"))
    )
    (net (code "83") (name "unconnected-(U1-VBUSD--Pad15)") (class "Default")
      (node (ref "U1") (pin "15") (pinfunction "VBUSD-_15") (pintype "bidirectional"))
    )
    (net (code "84") (name "unconnected-(U2-PA3-Pad17)") (class "Default")
      (node (ref "U2") (pin "17") (pinfunction "PA3_17") (pintype "bidirectional"))
    )
    (net (code "85") (name "unconnected-(U2-PA4-Pad20)") (class "Default")
      (node (ref "U2") (pin "20") (pinfunction "PA4_20") (pintype "bidirectional"))
    )
    (net (code "86") (name "unconnected-(U2-PA5-Pad21)") (class "Default")
      (node (ref "U2") (pin "21") (pinfunction "PA5_21") (pintype "bidirectional"))
    )
    (net (code "87") (name "unconnected-(U2-PA6-Pad22)") (class "Default")
      (node (ref "U2") (pin "22") (pinfunction "PA6_22") (pintype "bidirectional"))
    )
    (net (code "88") (name "unconnected-(U2-PA7-Pad23)") (class "Default")
      (node (ref "U2") (pin "23") (pinfunction "PA7_23") (pintype "bidirectional"))
    )
    (net (code "89") (name "unconnected-(U2-PA8-Pad41)") (class "Default")
      (node (ref "U2") (pin "41") (pinfunction "PA8_41") (pintype "bidirectional"))
    )
    (net (code "90") (name "unconnected-(U2-PA10-Pad43)") (class "Default")
      (node (ref "U2") (pin "43") (pinfunction "PA10_43") (pintype "bidirectional"))
    )
    (net (code "91") (name "unconnected-(U2-PA15-Pad50)") (class "Default")
      (node (ref "U2") (pin "50") (pinfunction "PA15_50") (pintype "bidirectional"))
    )
    (net (code "92") (name "unconnected-(U2-PB0-Pad26)") (class "Default")
      (node (ref "U2") (pin "26") (pinfunction "PB0_26") (pintype "bidirectional"))
    )
    (net (code "93") (name "unconnected-(U2-PB1-Pad27)") (class "Default")
      (node (ref "U2") (pin "27") (pinfunction "PB1_27") (pintype "bidirectional"))
    )
    (net (code "94") (name "unconnected-(U2-PB3-Pad55)") (class "Default")
      (node (ref "U2") (pin "55") (pinfunction "PB3_55") (pintype "bidirectional"))
    )
    (net (code "95") (name "unconnected-(U2-PB4-Pad56)") (class "Default")
      (node (ref "U2") (pin "56") (pinfunction "PB4_56") (pintype "bidirectional"))
    )
    (net (code "96") (name "unconnected-(U2-PB5-Pad57)") (class "Default")
      (node (ref "U2") (pin "57") (pinfunction "PB5_57") (pintype "bidirectional"))
    )
    (net (code "97") (name "unconnected-(U2-PB14-Pad35)") (class "Default")
      (node (ref "U2") (pin "35") (pinfunction "PB14_35") (pintype "bidirectional"))
    )
    (net (code "98") (name "unconnected-(U2-PC0-Pad8)") (class "Default")
      (node (ref "U2") (pin "8") (pinfunction "PC0_8") (pintype "bidirectional"))
    )
    (net (code "99") (name "unconnected-(U2-PC1-Pad9)") (class "Default")
      (node (ref "U2") (pin "9") (pinfunction "PC1_9") (pintype "bidirectional"))
    )
    (net (code "100") (name "unconnected-(U2-PC2-Pad10)") (class "Default")
      (node (ref "U2") (pin "10") (pinfunction "PC2_10") (pintype "bidirectional"))
    )
    (net (code "101") (name "unconnected-(U2-PC3-Pad11)") (class "Default")
      (node (ref "U2") (pin "11") (pinfunction "PC3_11") (pintype "bidirectional"))
    )
    (net (code "102") (name "unconnected-(U2-PC4-Pad24)") (class "Default")
      (node (ref "U2") (pin "24") (pinfunction "PC4_24") (pintype "bidirectional"))
    )
    (net (code "103") (name "unconnected-(U2-PC5-Pad25)") (class "Default")
      (node (ref "U2") (pin "25") (pinfunction "PC5_25") (pintype "bidirectional"))
    )
    (net (code "104") (name "unconnected-(U2-PC6-Pad37)") (class "Default")
      (node (ref "U2") (pin "37") (pinfunction "PC6_37") (pintype "bidirectional"))
    )
    (net (code "105") (name "unconnected-(U2-PC7-Pad38)") (class "Default")
      (node (ref "U2") (pin "38") (pinfunction "PC7_38") (pintype "bidirectional"))
    )
    (net (code "106") (name "unconnected-(U2-PC13-Pad2)") (class "Default")
      (node (ref "U2") (pin "2") (pinfunction "PC13_2") (pintype "bidirectional"))
    )
    (net (code "107") (name "unconnected-(U2-PC14-Pad3)") (class "Default")
      (node (ref "U2") (pin "3") (pinfunction "PC14_3") (pintype "bidirectional"))
    )
    (net (code "108") (name "unconnected-(U2-PC15-Pad4)") (class "Default")
      (node (ref "U2") (pin "4") (pinfunction "PC15_4") (pintype "bidirectional"))
    )
    (net (code "109") (name "unconnected-(U2-USB_DM(PA11)-Pad44)") (class "Default")
      (node (ref "U2") (pin "44") (pinfunction "USB_DM(PA11)_44") (pintype "bidirectional"))
    )
    (net (code "110") (name "unconnected-(U2-USB_DP(PA12)-Pad45)") (class "Default")
      (node (ref "U2") (pin "45") (pinfunction "USB_DP(PA12)_45") (pintype "bidirectional"))
    )
  )
)
